# volume_ctrl.net
KiCad netlist of a schematic drawn in EAGLE
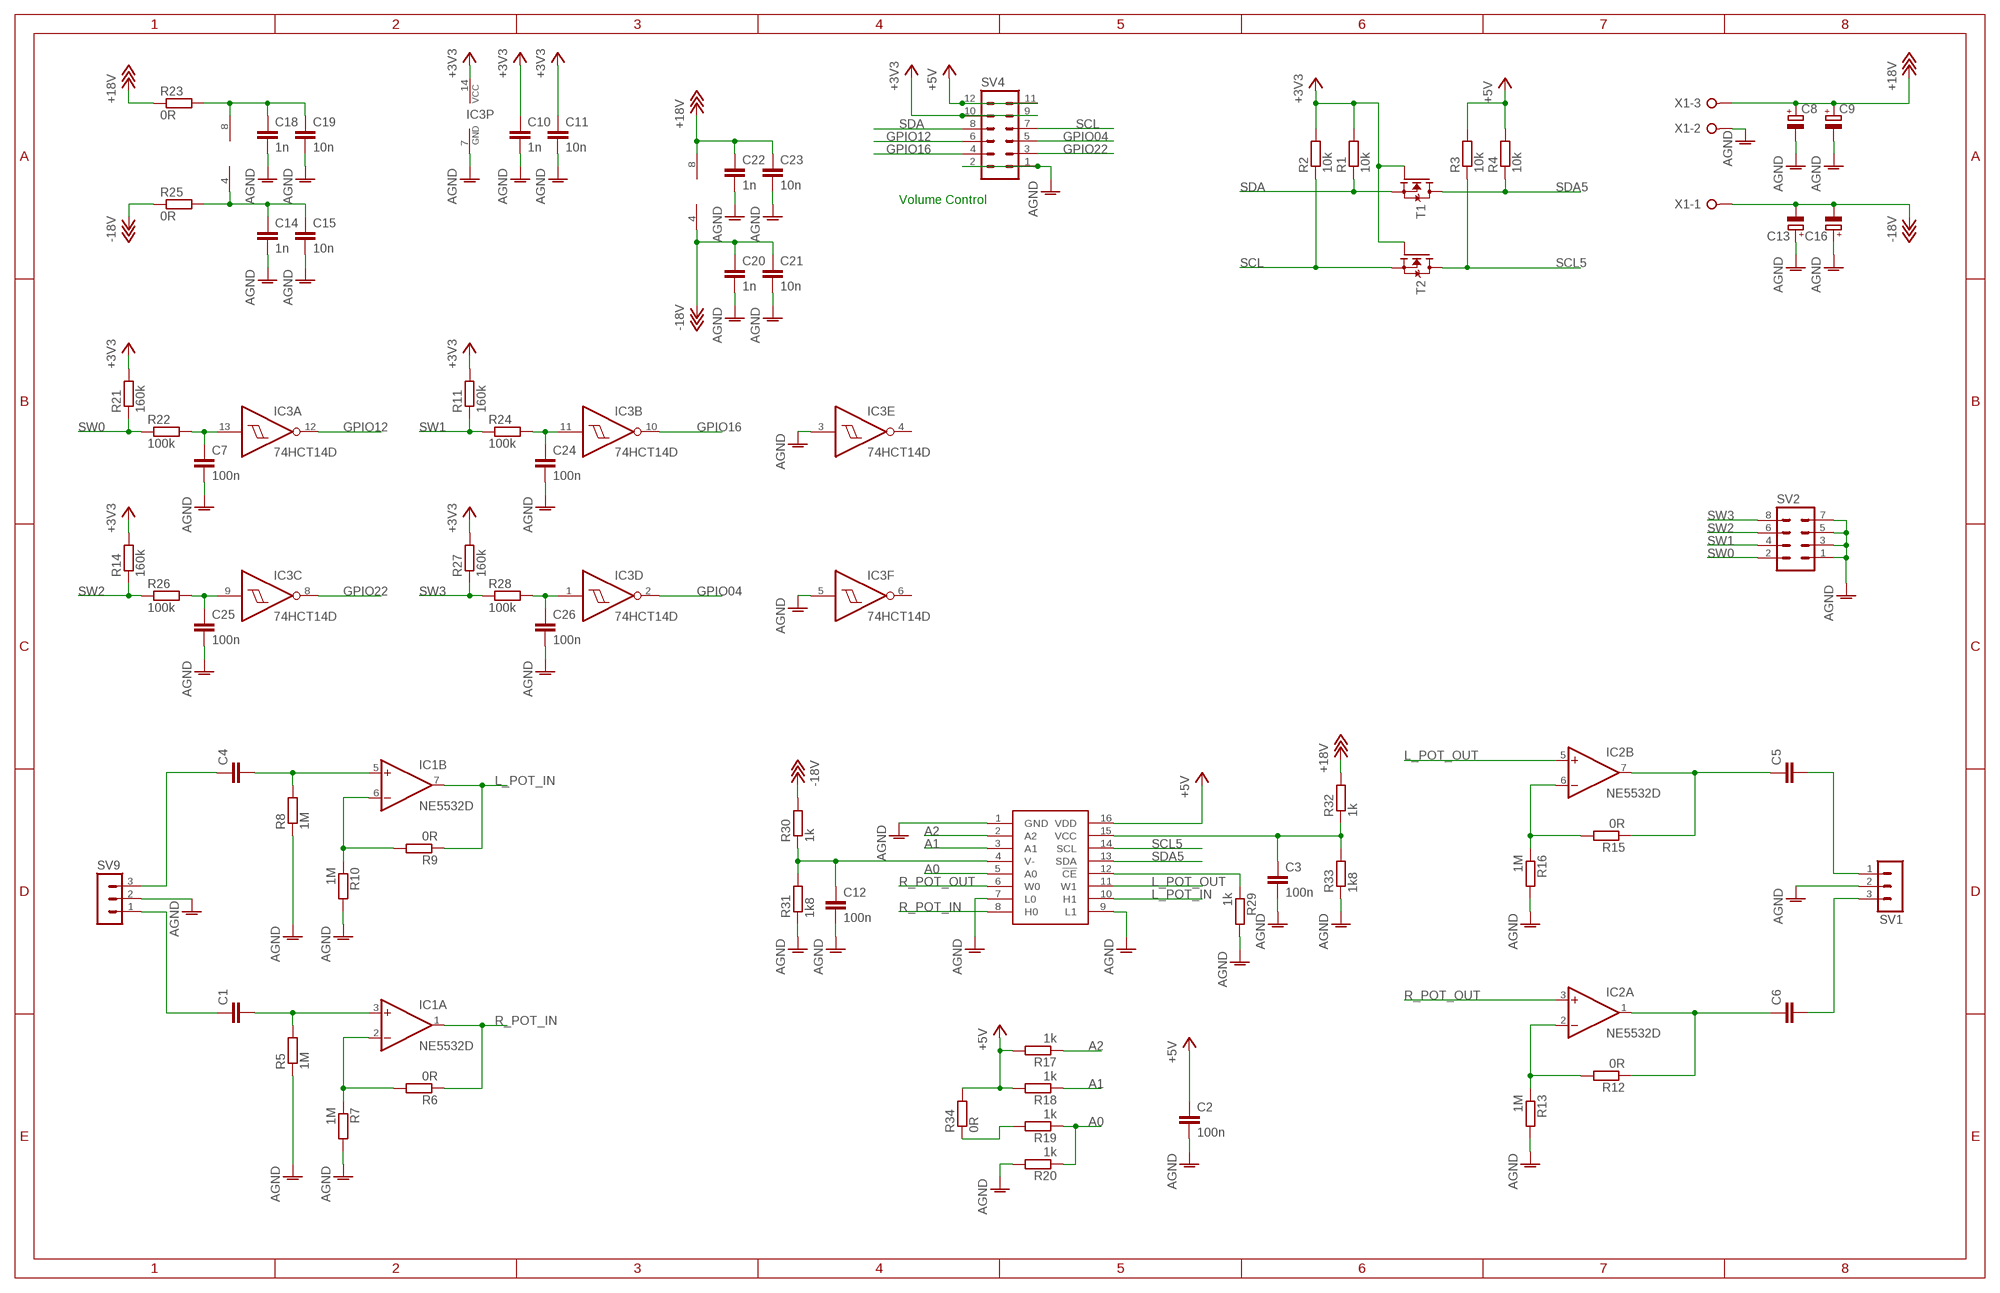
[diagram p0: schematic, sheet 1]

(export (version "E")
  (design (tool "Eeschema 10.0.6"))
  (components
    (comp (ref "C1")
      (value "C22/7")
      (footprint "eagle-import:C22.5B7")
      (libsource (lib "eagle-import") (part "C22/7"))
    )
    (comp (ref "C2")
      (value "100n")
      (footprint "eagle-import:C0603")
      (libsource (lib "eagle-import") (part "C-EUC0603"))
    )
    (comp (ref "C3")
      (value "100n")
      (footprint "eagle-import:C0603")
      (libsource (lib "eagle-import") (part "C-EUC0603"))
    )
    (comp (ref "C4")
      (value "C22/7")
      (footprint "eagle-import:C22.5B7")
      (libsource (lib "eagle-import") (part "C22/7"))
    )
    (comp (ref "C5")
      (value "C22/7")
      (footprint "eagle-import:C22.5B7")
      (libsource (lib "eagle-import") (part "C22/7"))
    )
    (comp (ref "C6")
      (value "C22/7")
      (footprint "eagle-import:C22.5B7")
      (libsource (lib "eagle-import") (part "C22/7"))
    )
    (comp (ref "C7")
      (value "100n")
      (footprint "eagle-import:C0603")
      (libsource (lib "eagle-import") (part "C-EUC0603"))
    )
    (comp (ref "C8")
      (value "CPOL-EUE5-10.5")
      (footprint "eagle-import:E5-10,5")
      (libsource (lib "eagle-import") (part "CPOL-EUE5-10.5"))
    )
    (comp (ref "C9")
      (value "CPOL-EUE5-10.5")
      (footprint "eagle-import:E5-10,5")
      (libsource (lib "eagle-import") (part "CPOL-EUE5-10.5"))
    )
    (comp (ref "C10")
      (value "1n")
      (footprint "eagle-import:C0603")
      (libsource (lib "eagle-import") (part "C-EUC0603"))
    )
    (comp (ref "C11")
      (value "10n")
      (footprint "eagle-import:C0603")
      (libsource (lib "eagle-import") (part "C-EUC0603"))
    )
    (comp (ref "C12")
      (value "100n")
      (footprint "eagle-import:C0603")
      (libsource (lib "eagle-import") (part "C-EUC0603"))
    )
    (comp (ref "C13")
      (value "CPOL-EUE5-10.5")
      (footprint "eagle-import:E5-10,5")
      (libsource (lib "eagle-import") (part "CPOL-EUE5-10.5"))
    )
    (comp (ref "C14")
      (value "1n")
      (footprint "eagle-import:C0603")
      (libsource (lib "eagle-import") (part "C-EUC0603"))
    )
    (comp (ref "C15")
      (value "10n")
      (footprint "eagle-import:C0603")
      (libsource (lib "eagle-import") (part "C-EUC0603"))
    )
    (comp (ref "C16")
      (value "CPOL-EUE5-10.5")
      (footprint "eagle-import:E5-10,5")
      (libsource (lib "eagle-import") (part "CPOL-EUE5-10.5"))
    )
    (comp (ref "C18")
      (value "1n")
      (footprint "eagle-import:C0603")
      (libsource (lib "eagle-import") (part "C-EUC0603"))
    )
    (comp (ref "C19")
      (value "10n")
      (footprint "eagle-import:C0603")
      (libsource (lib "eagle-import") (part "C-EUC0603"))
    )
    (comp (ref "C20")
      (value "1n")
      (footprint "eagle-import:C0603")
      (libsource (lib "eagle-import") (part "C-EUC0603"))
    )
    (comp (ref "C21")
      (value "10n")
      (footprint "eagle-import:C0603")
      (libsource (lib "eagle-import") (part "C-EUC0603"))
    )
    (comp (ref "C22")
      (value "1n")
      (footprint "eagle-import:C0603")
      (libsource (lib "eagle-import") (part "C-EUC0603"))
    )
    (comp (ref "C23")
      (value "10n")
      (footprint "eagle-import:C0603")
      (libsource (lib "eagle-import") (part "C-EUC0603"))
    )
    (comp (ref "C24")
      (value "100n")
      (footprint "eagle-import:C0603")
      (libsource (lib "eagle-import") (part "C-EUC0603"))
    )
    (comp (ref "C25")
      (value "100n")
      (footprint "eagle-import:C0603")
      (libsource (lib "eagle-import") (part "C-EUC0603"))
    )
    (comp (ref "C26")
      (value "100n")
      (footprint "eagle-import:C0603")
      (libsource (lib "eagle-import") (part "C-EUC0603"))
    )
    (comp (ref "IC1")
      (value "NE5532D")
      (footprint "eagle-import:SO08")
      (libsource (lib "eagle-import") (part "NE5532D"))
    )
    (comp (ref "IC2")
      (value "NE5532D")
      (footprint "eagle-import:SO08")
      (libsource (lib "eagle-import") (part "NE5532D"))
    )
    (comp (ref "IC3")
      (value "74HCT14D")
      (footprint "eagle-import:SO14")
      (libsource (lib "eagle-import") (part "7414DHCT"))
    )
    (comp (ref "IC4")
      (value "DS1882")
      (footprint "eagle-import:SO16")
      (libsource (lib "eagle-import") (part "DS1882"))
    )
    (comp (ref "R1")
      (value "10k")
      (footprint "eagle-import:R0805")
      (libsource (lib "eagle-import") (part "resistor_R-EU_R0805"))
    )
    (comp (ref "R2")
      (value "10k")
      (footprint "eagle-import:R0805")
      (libsource (lib "eagle-import") (part "resistor_R-EU_R0805"))
    )
    (comp (ref "R3")
      (value "10k")
      (footprint "eagle-import:R0805")
      (libsource (lib "eagle-import") (part "resistor_R-EU_R0805"))
    )
    (comp (ref "R4")
      (value "10k")
      (footprint "eagle-import:R1206")
      (libsource (lib "eagle-import") (part "R-EU_R1206"))
    )
    (comp (ref "R5")
      (value "1M")
      (footprint "eagle-import:R0805")
      (libsource (lib "eagle-import") (part "resistor_R-EU_R0805"))
    )
    (comp (ref "R6")
      (value "0R")
      (footprint "eagle-import:R0805")
      (libsource (lib "eagle-import") (part "resistor_R-EU_R0805"))
    )
    (comp (ref "R7")
      (value "1M")
      (footprint "eagle-import:R0805")
      (libsource (lib "eagle-import") (part "resistor_R-EU_R0805"))
    )
    (comp (ref "R8")
      (value "1M")
      (footprint "eagle-import:R0805")
      (libsource (lib "eagle-import") (part "resistor_R-EU_R0805"))
    )
    (comp (ref "R9")
      (value "0R")
      (footprint "eagle-import:R0805")
      (libsource (lib "eagle-import") (part "resistor_R-EU_R0805"))
    )
    (comp (ref "R10")
      (value "1M")
      (footprint "eagle-import:R0805")
      (libsource (lib "eagle-import") (part "resistor_R-EU_R0805"))
    )
    (comp (ref "R11")
      (value "160k")
      (footprint "eagle-import:R1206")
      (libsource (lib "eagle-import") (part "R-EU_R1206"))
    )
    (comp (ref "R12")
      (value "0R")
      (footprint "eagle-import:R0805")
      (libsource (lib "eagle-import") (part "resistor_R-EU_R0805"))
    )
    (comp (ref "R13")
      (value "1M")
      (footprint "eagle-import:R0805")
      (libsource (lib "eagle-import") (part "resistor_R-EU_R0805"))
    )
    (comp (ref "R14")
      (value "160k")
      (footprint "eagle-import:R1206")
      (libsource (lib "eagle-import") (part "R-EU_R1206"))
    )
    (comp (ref "R15")
      (value "0R")
      (footprint "eagle-import:R0805")
      (libsource (lib "eagle-import") (part "resistor_R-EU_R0805"))
    )
    (comp (ref "R16")
      (value "1M")
      (footprint "eagle-import:R0805")
      (libsource (lib "eagle-import") (part "resistor_R-EU_R0805"))
    )
    (comp (ref "R17")
      (value "1k")
      (footprint "eagle-import:R0805")
      (libsource (lib "eagle-import") (part "resistor_R-EU_R0805"))
    )
    (comp (ref "R18")
      (value "1k")
      (footprint "eagle-import:R0805")
      (libsource (lib "eagle-import") (part "resistor_R-EU_R0805"))
    )
    (comp (ref "R19")
      (value "1k")
      (footprint "eagle-import:R0805")
      (libsource (lib "eagle-import") (part "resistor_R-EU_R0805"))
    )
    (comp (ref "R20")
      (value "1k")
      (footprint "eagle-import:R0805")
      (libsource (lib "eagle-import") (part "resistor_R-EU_R0805"))
    )
    (comp (ref "R21")
      (value "160k")
      (footprint "eagle-import:R0603")
      (libsource (lib "eagle-import") (part "R-EU_R0603"))
    )
    (comp (ref "R22")
      (value "100k")
      (footprint "eagle-import:R0603")
      (libsource (lib "eagle-import") (part "R-EU_R0603"))
    )
    (comp (ref "R23")
      (value "0R")
      (footprint "eagle-import:R1206")
      (libsource (lib "eagle-import") (part "R-EU_R1206"))
    )
    (comp (ref "R24")
      (value "100k")
      (footprint "eagle-import:R0603")
      (libsource (lib "eagle-import") (part "R-EU_R0603"))
    )
    (comp (ref "R25")
      (value "0R")
      (footprint "eagle-import:R1206")
      (libsource (lib "eagle-import") (part "R-EU_R1206"))
    )
    (comp (ref "R26")
      (value "100k")
      (footprint "eagle-import:R0603")
      (libsource (lib "eagle-import") (part "R-EU_R0603"))
    )
    (comp (ref "R27")
      (value "160k")
      (footprint "eagle-import:R0603")
      (libsource (lib "eagle-import") (part "R-EU_R0603"))
    )
    (comp (ref "R28")
      (value "100k")
      (footprint "eagle-import:R0603")
      (libsource (lib "eagle-import") (part "R-EU_R0603"))
    )
    (comp (ref "R29")
      (value "1k")
      (footprint "eagle-import:R0805")
      (libsource (lib "eagle-import") (part "resistor_R-EU_R0805"))
    )
    (comp (ref "R30")
      (value "1k")
      (footprint "eagle-import:R0805")
      (libsource (lib "eagle-import") (part "resistor_R-EU_R0805"))
    )
    (comp (ref "R31")
      (value "1k8")
      (footprint "eagle-import:R0805")
      (libsource (lib "eagle-import") (part "resistor_R-EU_R0805"))
    )
    (comp (ref "R32")
      (value "1k")
      (footprint "eagle-import:R0805")
      (libsource (lib "eagle-import") (part "resistor_R-EU_R0805"))
    )
    (comp (ref "R33")
      (value "1k8")
      (footprint "eagle-import:R0805")
      (libsource (lib "eagle-import") (part "resistor_R-EU_R0805"))
    )
    (comp (ref "R34")
      (value "0R")
      (footprint "eagle-import:R1206")
      (libsource (lib "eagle-import") (part "R-EU_R1206"))
    )
    (comp (ref "SV1")
      (value "MA03-1")
      (footprint "eagle-import:MA03-1")
      (libsource (lib "eagle-import") (part "MA03-1"))
    )
    (comp (ref "SV2")
      (value "MA04-2")
      (footprint "eagle-import:MA04-2")
      (libsource (lib "eagle-import") (part "MA04-2"))
    )
    (comp (ref "SV4")
      (value "MA06-2")
      (footprint "eagle-import:MA06-2")
      (libsource (lib "eagle-import") (part "MA06-2"))
    )
    (comp (ref "SV9")
      (value "MA03-1")
      (footprint "eagle-import:MA03-1")
      (libsource (lib "eagle-import") (part "MA03-1"))
    )
    (comp (ref "T1")
      (value "MOSFET-N-SOT23")
      (footprint "eagle-import:SOT23")
      (libsource (lib "eagle-import") (part "MOSFET-N-SOT23"))
    )
    (comp (ref "T2")
      (value "MOSFET-N-SOT23")
      (footprint "eagle-import:SOT23")
      (libsource (lib "eagle-import") (part "MOSFET-N-SOT23"))
    )
    (comp (ref "X1")
      (value "W237-3E")
      (footprint "eagle-import:W237-3E")
      (libsource (lib "eagle-import") (part "W237-3E"))
    )
  )
  (nets
    (net (code "1") (name "+3V3") (class "Default")
      (node (ref "C10") (pin "1") (pinfunction "1_1") (pintype "passive"))
      (node (ref "C11") (pin "1") (pinfunction "1_1") (pintype "passive"))
      (node (ref "IC3") (pin "14") (pinfunction "VCC_14") (pintype "power_in"))
      (node (ref "R1") (pin "2") (pinfunction "2_2") (pintype "passive"))
      (node (ref "R11") (pin "2") (pinfunction "2_2") (pintype "passive"))
      (node (ref "R14") (pin "2") (pinfunction "2_2") (pintype "passive"))
      (node (ref "R2") (pin "2") (pinfunction "2_2") (pintype "passive"))
      (node (ref "R21") (pin "2") (pinfunction "2_2") (pintype "passive"))
      (node (ref "R27") (pin "2") (pinfunction "2_2") (pintype "passive"))
      (node (ref "SV4") (pin "10") (pinfunction "10_10") (pintype "passive"))
      (node (ref "SV4") (pin "9") (pinfunction "9_9") (pintype "passive"))
      (node (ref "T1") (pin "1") (pinfunction "G_1") (pintype "passive"))
      (node (ref "T2") (pin "1") (pinfunction "G_1") (pintype "passive"))
    )
    (net (code "2") (name "+5V") (class "Default")
      (node (ref "C2") (pin "1") (pinfunction "1_1") (pintype "passive"))
      (node (ref "IC4") (pin "16") (pinfunction "VDD_16") (pintype "power_in"))
      (node (ref "R17") (pin "2") (pinfunction "2_2") (pintype "passive"))
      (node (ref "R18") (pin "2") (pinfunction "2_2") (pintype "passive"))
      (node (ref "R3") (pin "2") (pinfunction "2_2") (pintype "passive"))
      (node (ref "R34") (pin "2") (pinfunction "2_2") (pintype "passive"))
      (node (ref "R4") (pin "2") (pinfunction "2_2") (pintype "passive"))
      (node (ref "SV4") (pin "11") (pinfunction "11_11") (pintype "passive"))
      (node (ref "SV4") (pin "12") (pinfunction "12_12") (pintype "passive"))
    )
    (net (code "3") (name "+18V") (class "Default")
      (node (ref "C22") (pin "1") (pinfunction "1_1") (pintype "passive"))
      (node (ref "C23") (pin "1") (pinfunction "1_1") (pintype "passive"))
      (node (ref "C8") (pin "+") (pinfunction "+_+") (pintype "passive"))
      (node (ref "C9") (pin "+") (pinfunction "+_+") (pintype "passive"))
      (node (ref "IC2") (pin "8") (pinfunction "V+_8") (pintype "power_in"))
      (node (ref "R23") (pin "1") (pinfunction "1_1") (pintype "passive"))
      (node (ref "R32") (pin "2") (pinfunction "2_2") (pintype "passive"))
      (node (ref "X1") (pin "3") (pinfunction "KL_3") (pintype "passive"))
    )
    (net (code "4") (name "-18V") (class "Default")
      (node (ref "C13") (pin "-") (pinfunction "-_-") (pintype "passive"))
      (node (ref "C16") (pin "-") (pinfunction "-_-") (pintype "passive"))
      (node (ref "C20") (pin "1") (pinfunction "1_1") (pintype "passive"))
      (node (ref "C21") (pin "1") (pinfunction "1_1") (pintype "passive"))
      (node (ref "IC2") (pin "4") (pinfunction "V-_4") (pintype "power_in"))
      (node (ref "R25") (pin "1") (pinfunction "1_1") (pintype "passive"))
      (node (ref "R30") (pin "2") (pinfunction "2_2") (pintype "passive"))
      (node (ref "X1") (pin "1") (pinfunction "KL_1") (pintype "passive"))
    )
    (net (code "5") (name "/A0") (class "Default")
      (node (ref "IC4") (pin "5") (pinfunction "A0_5") (pintype "bidirectional"))
      (node (ref "R19") (pin "1") (pinfunction "1_1") (pintype "passive"))
      (node (ref "R20") (pin "1") (pinfunction "1_1") (pintype "passive"))
    )
    (net (code "6") (name "/A1") (class "Default")
      (node (ref "IC4") (pin "3") (pinfunction "A1_3") (pintype "bidirectional"))
      (node (ref "R18") (pin "1") (pinfunction "1_1") (pintype "passive"))
    )
    (net (code "7") (name "/A2") (class "Default")
      (node (ref "IC4") (pin "2") (pinfunction "A2_2") (pintype "bidirectional"))
      (node (ref "R17") (pin "1") (pinfunction "1_1") (pintype "passive"))
    )
    (net (code "8") (name "/GPIO04") (class "Default")
      (node (ref "IC3") (pin "2") (pinfunction "O_2") (pintype "output"))
      (node (ref "SV4") (pin "5") (pinfunction "5_5") (pintype "passive"))
    )
    (net (code "9") (name "/GPIO12") (class "Default")
      (node (ref "IC3") (pin "12") (pinfunction "O_12") (pintype "output"))
      (node (ref "SV4") (pin "6") (pinfunction "6_6") (pintype "passive"))
    )
    (net (code "10") (name "/GPIO16") (class "Default")
      (node (ref "IC3") (pin "10") (pinfunction "O_10") (pintype "output"))
      (node (ref "SV4") (pin "4") (pinfunction "4_4") (pintype "passive"))
    )
    (net (code "11") (name "/GPIO22") (class "Default")
      (node (ref "IC3") (pin "8") (pinfunction "O_8") (pintype "output"))
      (node (ref "SV4") (pin "3") (pinfunction "3_3") (pintype "passive"))
    )
    (net (code "12") (name "/L_POT_IN") (class "Default")
      (node (ref "IC1") (pin "7") (pinfunction "OUT_7") (pintype "output"))
      (node (ref "IC4") (pin "10") (pinfunction "H1_10") (pintype "bidirectional"))
      (node (ref "R9") (pin "1") (pinfunction "1_1") (pintype "passive"))
    )
    (net (code "13") (name "/L_POT_OUT") (class "Default")
      (node (ref "IC2") (pin "5") (pinfunction "+IN_5") (pintype "input"))
      (node (ref "IC4") (pin "11") (pinfunction "W1_11") (pintype "bidirectional"))
    )
    (net (code "14") (name "/R_POT_IN") (class "Default")
      (node (ref "IC1") (pin "1") (pinfunction "OUT_1") (pintype "output"))
      (node (ref "IC4") (pin "8") (pinfunction "H0_8") (pintype "bidirectional"))
      (node (ref "R6") (pin "1") (pinfunction "1_1") (pintype "passive"))
    )
    (net (code "15") (name "/R_POT_OUT") (class "Default")
      (node (ref "IC2") (pin "3") (pinfunction "+IN_3") (pintype "input"))
      (node (ref "IC4") (pin "6") (pinfunction "W0_6") (pintype "bidirectional"))
    )
    (net (code "16") (name "/SCL") (class "Default")
      (node (ref "R2") (pin "1") (pinfunction "1_1") (pintype "passive"))
      (node (ref "SV4") (pin "7") (pinfunction "7_7") (pintype "passive"))
      (node (ref "T2") (pin "2") (pinfunction "S_2") (pintype "passive"))
    )
    (net (code "17") (name "/SCL5") (class "Default")
      (node (ref "IC4") (pin "14") (pinfunction "SCL_14") (pintype "bidirectional"))
      (node (ref "R3") (pin "1") (pinfunction "1_1") (pintype "passive"))
      (node (ref "T2") (pin "3") (pinfunction "D_3") (pintype "passive"))
    )
    (net (code "18") (name "/SDA") (class "Default")
      (node (ref "R1") (pin "1") (pinfunction "1_1") (pintype "passive"))
      (node (ref "SV4") (pin "8") (pinfunction "8_8") (pintype "passive"))
      (node (ref "T1") (pin "2") (pinfunction "S_2") (pintype "passive"))
    )
    (net (code "19") (name "/SDA5") (class "Default")
      (node (ref "IC4") (pin "13") (pinfunction "SDA_13") (pintype "bidirectional"))
      (node (ref "R4") (pin "1") (pinfunction "1_1") (pintype "passive"))
      (node (ref "T1") (pin "3") (pinfunction "D_3") (pintype "passive"))
    )
    (net (code "20") (name "/SW0") (class "Default")
      (node (ref "R21") (pin "1") (pinfunction "1_1") (pintype "passive"))
      (node (ref "R22") (pin "1") (pinfunction "1_1") (pintype "passive"))
      (node (ref "SV2") (pin "2") (pinfunction "2_2") (pintype "passive"))
    )
    (net (code "21") (name "/SW1") (class "Default")
      (node (ref "R11") (pin "1") (pinfunction "1_1") (pintype "passive"))
      (node (ref "R24") (pin "1") (pinfunction "1_1") (pintype "passive"))
      (node (ref "SV2") (pin "4") (pinfunction "4_4") (pintype "passive"))
    )
    (net (code "22") (name "/SW2") (class "Default")
      (node (ref "R14") (pin "1") (pinfunction "1_1") (pintype "passive"))
      (node (ref "R26") (pin "1") (pinfunction "1_1") (pintype "passive"))
      (node (ref "SV2") (pin "6") (pinfunction "6_6") (pintype "passive"))
    )
    (net (code "23") (name "/SW3") (class "Default")
      (node (ref "R27") (pin "1") (pinfunction "1_1") (pintype "passive"))
      (node (ref "R28") (pin "1") (pinfunction "1_1") (pintype "passive"))
      (node (ref "SV2") (pin "8") (pinfunction "8_8") (pintype "passive"))
    )
    (net (code "24") (name "AGND") (class "Default")
      (node (ref "C10") (pin "2") (pinfunction "2_2") (pintype "passive"))
      (node (ref "C11") (pin "2") (pinfunction "2_2") (pintype "passive"))
      (node (ref "C12") (pin "2") (pinfunction "2_2") (pintype "passive"))
      (node (ref "C13") (pin "+") (pinfunction "+_+") (pintype "passive"))
      (node (ref "C14") (pin "2") (pinfunction "2_2") (pintype "passive"))
      (node (ref "C15") (pin "2") (pinfunction "2_2") (pintype "passive"))
      (node (ref "C16") (pin "+") (pinfunction "+_+") (pintype "passive"))
      (node (ref "C18") (pin "2") (pinfunction "2_2") (pintype "passive"))
      (node (ref "C19") (pin "2") (pinfunction "2_2") (pintype "passive"))
      (node (ref "C2") (pin "2") (pinfunction "2_2") (pintype "passive"))
      (node (ref "C20") (pin "2") (pinfunction "2_2") (pintype "passive"))
      (node (ref "C21") (pin "2") (pinfunction "2_2") (pintype "passive"))
      (node (ref "C22") (pin "2") (pinfunction "2_2") (pintype "passive"))
      (node (ref "C23") (pin "2") (pinfunction "2_2") (pintype "passive"))
      (node (ref "C24") (pin "2") (pinfunction "2_2") (pintype "passive"))
      (node (ref "C25") (pin "2") (pinfunction "2_2") (pintype "passive"))
      (node (ref "C26") (pin "2") (pinfunction "2_2") (pintype "passive"))
      (node (ref "C3") (pin "2") (pinfunction "2_2") (pintype "passive"))
      (node (ref "C7") (pin "2") (pinfunction "2_2") (pintype "passive"))
      (node (ref "C8") (pin "-") (pinfunction "-_-") (pintype "passive"))
      (node (ref "C9") (pin "-") (pinfunction "-_-") (pintype "passive"))
      (node (ref "IC3") (pin "3") (pinfunction "I_3") (pintype "input"))
      (node (ref "IC3") (pin "5") (pinfunction "I_5") (pintype "input"))
      (node (ref "IC3") (pin "7") (pinfunction "GND_7") (pintype "power_in"))
      (node (ref "IC4") (pin "1") (pinfunction "GND_1") (pintype "power_in"))
      (node (ref "IC4") (pin "7") (pinfunction "L0_7") (pintype "bidirectional"))
      (node (ref "IC4") (pin "9") (pinfunction "L1_9") (pintype "bidirectional"))
      (node (ref "R10") (pin "2") (pinfunction "2_2") (pintype "passive"))
      (node (ref "R13") (pin "2") (pinfunction "2_2") (pintype "passive"))
      (node (ref "R16") (pin "2") (pinfunction "2_2") (pintype "passive"))
      (node (ref "R20") (pin "2") (pinfunction "2_2") (pintype "passive"))
      (node (ref "R29") (pin "2") (pinfunction "2_2") (pintype "passive"))
      (node (ref "R31") (pin "1") (pinfunction "1_1") (pintype "passive"))
      (node (ref "R33") (pin "1") (pinfunction "1_1") (pintype "passive"))
      (node (ref "R5") (pin "1") (pinfunction "1_1") (pintype "passive"))
      (node (ref "R7") (pin "2") (pinfunction "2_2") (pintype "passive"))
      (node (ref "R8") (pin "1") (pinfunction "1_1") (pintype "passive"))
      (node (ref "SV1") (pin "2") (pinfunction "2_2") (pintype "passive"))
      (node (ref "SV2") (pin "1") (pinfunction "1_1") (pintype "passive"))
      (node (ref "SV2") (pin "3") (pinfunction "3_3") (pintype "passive"))
      (node (ref "SV2") (pin "5") (pinfunction "5_5") (pintype "passive"))
      (node (ref "SV2") (pin "7") (pinfunction "7_7") (pintype "passive"))
      (node (ref "SV4") (pin "1") (pinfunction "1_1") (pintype "passive"))
      (node (ref "SV4") (pin "2") (pinfunction "2_2") (pintype "passive"))
      (node (ref "SV9") (pin "2") (pinfunction "2_2") (pintype "passive"))
      (node (ref "X1") (pin "2") (pinfunction "KL_2") (pintype "passive"))
    )
    (net (code "25") (name "Net-(C1-Pad1)") (class "Default")
      (node (ref "C1") (pin "1") (pinfunction "1_1") (pintype "passive"))
      (node (ref "SV9") (pin "1") (pinfunction "1_1") (pintype "passive"))
    )
    (net (code "26") (name "Net-(C4-Pad1)") (class "Default")
      (node (ref "C4") (pin "1") (pinfunction "1_1") (pintype "passive"))
      (node (ref "SV9") (pin "3") (pinfunction "3_3") (pintype "passive"))
    )
    (net (code "27") (name "Net-(C5-Pad2)") (class "Default")
      (node (ref "C5") (pin "2") (pinfunction "2_2") (pintype "passive"))
      (node (ref "SV1") (pin "1") (pinfunction "1_1") (pintype "passive"))
    )
    (net (code "28") (name "Net-(C6-Pad2)") (class "Default")
      (node (ref "C6") (pin "2") (pinfunction "2_2") (pintype "passive"))
      (node (ref "SV1") (pin "3") (pinfunction "3_3") (pintype "passive"))
    )
    (net (code "29") (name "Net-(IC1A-+IN)") (class "Default")
      (node (ref "C1") (pin "2") (pinfunction "2_2") (pintype "passive"))
      (node (ref "IC1") (pin "3") (pinfunction "+IN_3") (pintype "input"))
      (node (ref "R5") (pin "2") (pinfunction "2_2") (pintype "passive"))
    )
    (net (code "30") (name "Net-(IC1A--IN)") (class "Default")
      (node (ref "IC1") (pin "2") (pinfunction "-IN_2") (pintype "input"))
      (node (ref "R6") (pin "2") (pinfunction "2_2") (pintype "passive"))
      (node (ref "R7") (pin "1") (pinfunction "1_1") (pintype "passive"))
    )
    (net (code "31") (name "Net-(IC1B-+IN)") (class "Default")
      (node (ref "C4") (pin "2") (pinfunction "2_2") (pintype "passive"))
      (node (ref "IC1") (pin "5") (pinfunction "+IN_5") (pintype "input"))
      (node (ref "R8") (pin "2") (pinfunction "2_2") (pintype "passive"))
    )
    (net (code "32") (name "Net-(IC1B--IN)") (class "Default")
      (node (ref "IC1") (pin "6") (pinfunction "-IN_6") (pintype "input"))
      (node (ref "R10") (pin "1") (pinfunction "1_1") (pintype "passive"))
      (node (ref "R9") (pin "2") (pinfunction "2_2") (pintype "passive"))
    )
    (net (code "33") (name "Net-(IC1C-V+)") (class "Default")
      (node (ref "C18") (pin "1") (pinfunction "1_1") (pintype "passive"))
      (node (ref "C19") (pin "1") (pinfunction "1_1") (pintype "passive"))
      (node (ref "IC1") (pin "8") (pinfunction "V+_8") (pintype "power_in"))
      (node (ref "R23") (pin "2") (pinfunction "2_2") (pintype "passive"))
    )
    (net (code "34") (name "Net-(IC1C-V-)") (class "Default")
      (node (ref "C14") (pin "1") (pinfunction "1_1") (pintype "passive"))
      (node (ref "C15") (pin "1") (pinfunction "1_1") (pintype "passive"))
      (node (ref "IC1") (pin "4") (pinfunction "V-_4") (pintype "power_in"))
      (node (ref "R25") (pin "2") (pinfunction "2_2") (pintype "passive"))
    )
    (net (code "35") (name "Net-(IC2A--IN)") (class "Default")
      (node (ref "IC2") (pin "2") (pinfunction "-IN_2") (pintype "input"))
      (node (ref "R12") (pin "2") (pinfunction "2_2") (pintype "passive"))
      (node (ref "R13") (pin "1") (pinfunction "1_1") (pintype "passive"))
    )
    (net (code "36") (name "Net-(IC2A-OUT)") (class "Default")
      (node (ref "C6") (pin "1") (pinfunction "1_1") (pintype "passive"))
      (node (ref "IC2") (pin "1") (pinfunction "OUT_1") (pintype "output"))
      (node (ref "R12") (pin "1") (pinfunction "1_1") (pintype "passive"))
    )
    (net (code "37") (name "Net-(IC2B--IN)") (class "Default")
      (node (ref "IC2") (pin "6") (pinfunction "-IN_6") (pintype "input"))
      (node (ref "R15") (pin "2") (pinfunction "2_2") (pintype "passive"))
      (node (ref "R16") (pin "1") (pinfunction "1_1") (pintype "passive"))
    )
    (net (code "38") (name "Net-(IC2B-OUT)") (class "Default")
      (node (ref "C5") (pin "1") (pinfunction "1_1") (pintype "passive"))
      (node (ref "IC2") (pin "7") (pinfunction "OUT_7") (pintype "output"))
      (node (ref "R15") (pin "1") (pinfunction "1_1") (pintype "passive"))
    )
    (net (code "39") (name "Net-(IC3A-I)") (class "Default")
      (node (ref "C7") (pin "1") (pinfunction "1_1") (pintype "passive"))
      (node (ref "IC3") (pin "13") (pinfunction "I_13") (pintype "input"))
      (node (ref "R22") (pin "2") (pinfunction "2_2") (pintype "passive"))
    )
    (net (code "40") (name "Net-(IC3B-I)") (class "Default")
      (node (ref "C24") (pin "1") (pinfunction "1_1") (pintype "passive"))
      (node (ref "IC3") (pin "11") (pinfunction "I_11") (pintype "input"))
      (node (ref "R24") (pin "2") (pinfunction "2_2") (pintype "passive"))
    )
    (net (code "41") (name "Net-(IC3C-I)") (class "Default")
      (node (ref "C25") (pin "1") (pinfunction "1_1") (pintype "passive"))
      (node (ref "IC3") (pin "9") (pinfunction "I_9") (pintype "input"))
      (node (ref "R26") (pin "2") (pinfunction "2_2") (pintype "passive"))
    )
    (net (code "42") (name "Net-(IC3D-I)") (class "Default")
      (node (ref "C26") (pin "1") (pinfunction "1_1") (pintype "passive"))
      (node (ref "IC3") (pin "1") (pinfunction "I_1") (pintype "input"))
      (node (ref "R28") (pin "2") (pinfunction "2_2") (pintype "passive"))
    )
    (net (code "43") (name "Net-(IC4-V-)") (class "Default")
      (node (ref "C12") (pin "1") (pinfunction "1_1") (pintype "passive"))
      (node (ref "IC4") (pin "4") (pinfunction "V-_4") (pintype "power_in"))
      (node (ref "R30") (pin "1") (pinfunction "1_1") (pintype "passive"))
      (node (ref "R31") (pin "2") (pinfunction "2_2") (pintype "passive"))
    )
    (net (code "44") (name "Net-(IC4-VCC)") (class "Default")
      (node (ref "C3") (pin "1") (pinfunction "1_1") (pintype "passive"))
      (node (ref "IC4") (pin "15") (pinfunction "VCC_15") (pintype "power_in"))
      (node (ref "R32") (pin "1") (pinfunction "1_1") (pintype "passive"))
      (node (ref "R33") (pin "2") (pinfunction "2_2") (pintype "passive"))
    )
    (net (code "45") (name "Net-(IC4-~{CE})") (class "Default")
      (node (ref "IC4") (pin "12") (pinfunction "~{CE}_12") (pintype "bidirectional"))
      (node (ref "R29") (pin "1") (pinfunction "1_1") (pintype "passive"))
    )
    (net (code "46") (name "Net-(R19-Pad2)") (class "Default")
      (node (ref "R19") (pin "2") (pinfunction "2_2") (pintype "passive"))
      (node (ref "R34") (pin "1") (pinfunction "1_1") (pintype "passive"))
    )
    (net (code "47") (name "unconnected-(IC3E-O-Pad4)") (class "Default")
      (node (ref "IC3") (pin "4") (pinfunction "O_4") (pintype "output"))
    )
    (net (code "48") (name "unconnected-(IC3F-O-Pad6)") (class "Default")
      (node (ref "IC3") (pin "6") (pinfunction "O_6") (pintype "output"))
    )
  )
)
